# SCH_PCB_Dashboy_subboard_2023-03-20.net
KiCad netlist of a schematic drawn in EasyEDA
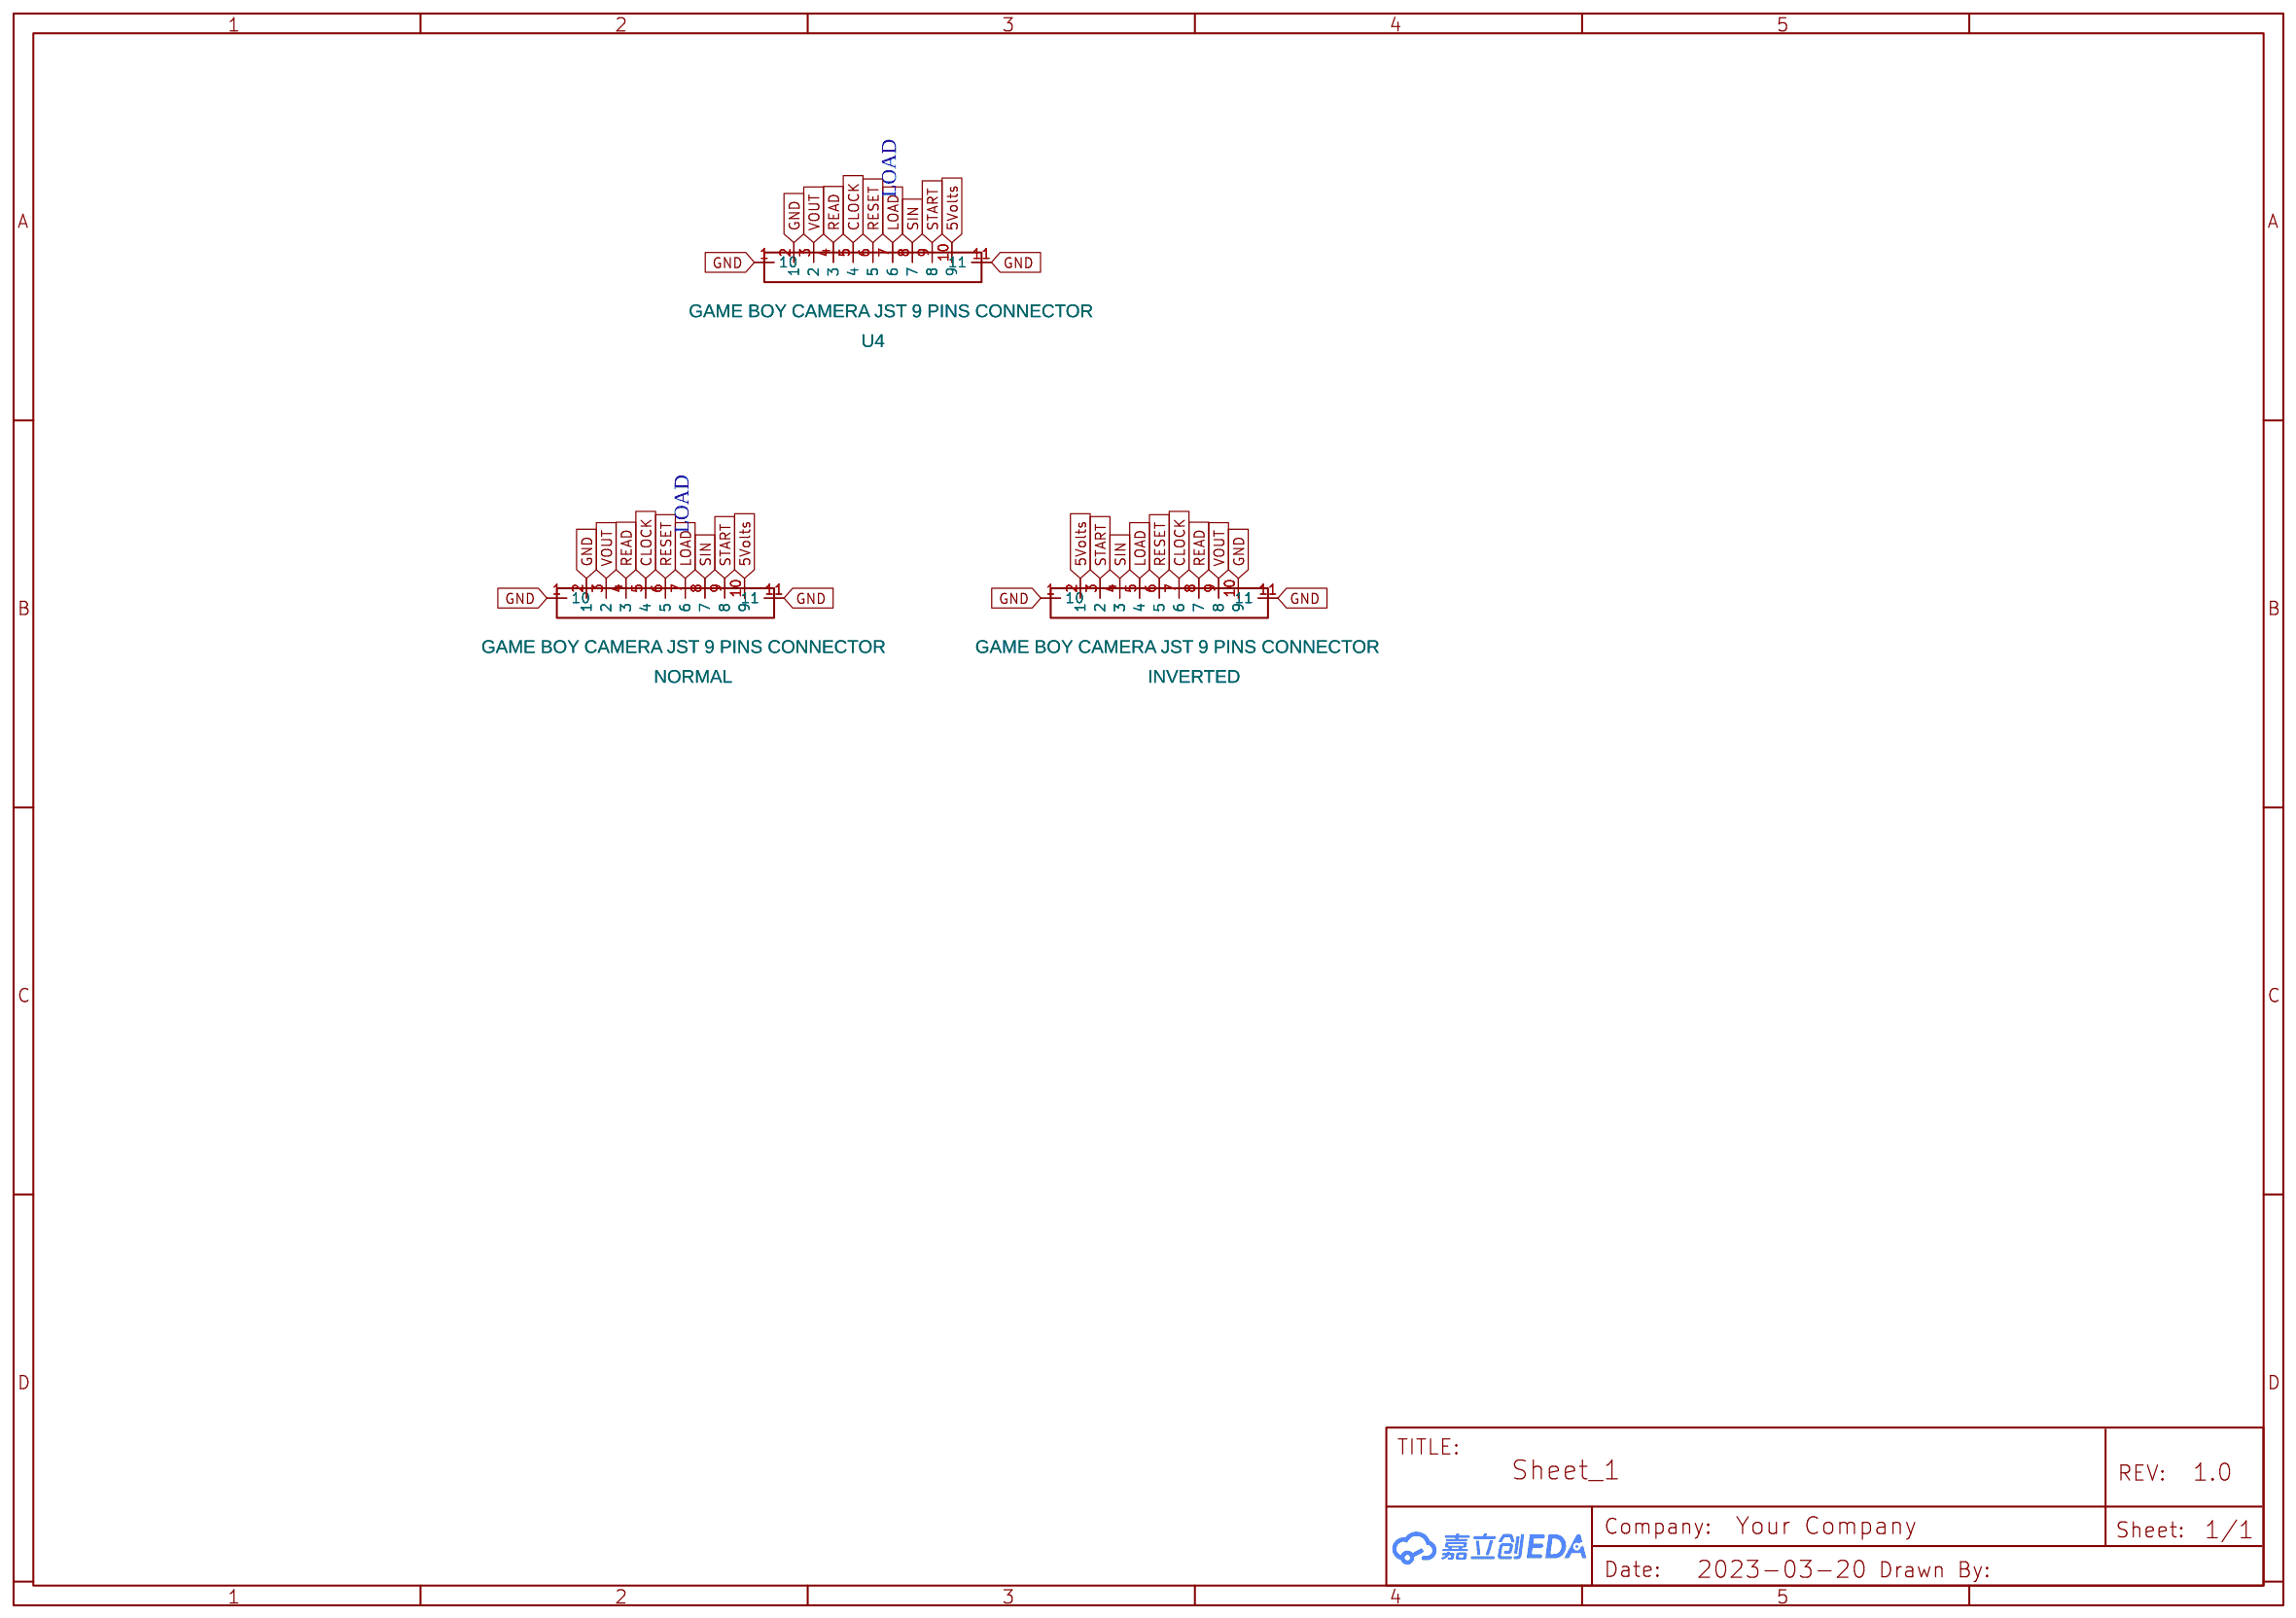
[diagram p0: schematic sheet]

(export (version "E")
  (design (tool "Eeschema 10.0.6"))
  (components
    (comp (ref "INVERTED")
      (value "GAME BOY CAMERA JST 9 PINS CONNECTOR")
      (libsource (lib "") (part "GAME BOY CAMERA JST 9 PINS CONNECTOR_1"))
    )
    (comp (ref "NORMAL")
      (value "GAME BOY CAMERA JST 9 PINS CONNECTOR")
      (libsource (lib "") (part "GAME BOY CAMERA JST 9 PINS CONNECTOR_2"))
    )
    (comp (ref "U4")
      (value "GAME BOY CAMERA JST 9 PINS CONNECTOR")
      (libsource (lib "") (part "GAME BOY CAMERA JST 9 PINS CONNECTOR"))
    )
  )
  (nets
    (net (code "1") (name "5Volts") (class "Default")
      (node (ref "INVERTED") (pin "2") (pinfunction "1_2") (pintype "unspecified"))
      (node (ref "NORMAL") (pin "10") (pinfunction "9_10") (pintype "unspecified"))
      (node (ref "U4") (pin "10") (pinfunction "9_10") (pintype "unspecified"))
    )
    (net (code "2") (name "CLOCK") (class "Default")
      (node (ref "INVERTED") (pin "7") (pinfunction "6_7") (pintype "unspecified"))
      (node (ref "NORMAL") (pin "5") (pinfunction "4_5") (pintype "unspecified"))
      (node (ref "U4") (pin "5") (pinfunction "4_5") (pintype "unspecified"))
    )
    (net (code "3") (name "GND") (class "Default")
      (node (ref "INVERTED") (pin "1") (pinfunction "10_1") (pintype "unspecified"))
      (node (ref "INVERTED") (pin "10") (pinfunction "9_10") (pintype "unspecified"))
      (node (ref "INVERTED") (pin "11") (pinfunction "11_11") (pintype "unspecified"))
      (node (ref "NORMAL") (pin "1") (pinfunction "10_1") (pintype "unspecified"))
      (node (ref "NORMAL") (pin "11") (pinfunction "11_11") (pintype "unspecified"))
      (node (ref "NORMAL") (pin "2") (pinfunction "1_2") (pintype "unspecified"))
      (node (ref "U4") (pin "1") (pinfunction "10_1") (pintype "unspecified"))
      (node (ref "U4") (pin "11") (pinfunction "11_11") (pintype "unspecified"))
      (node (ref "U4") (pin "2") (pinfunction "1_2") (pintype "unspecified"))
    )
    (net (code "4") (name "LOAD") (class "Default")
      (node (ref "INVERTED") (pin "5") (pinfunction "4_5") (pintype "unspecified"))
      (node (ref "NORMAL") (pin "7") (pinfunction "6_7") (pintype "unspecified"))
      (node (ref "U4") (pin "7") (pinfunction "6_7") (pintype "unspecified"))
    )
    (net (code "5") (name "READ") (class "Default")
      (node (ref "INVERTED") (pin "8") (pinfunction "7_8") (pintype "unspecified"))
      (node (ref "NORMAL") (pin "4") (pinfunction "3_4") (pintype "unspecified"))
      (node (ref "U4") (pin "4") (pinfunction "3_4") (pintype "unspecified"))
    )
    (net (code "6") (name "RESET") (class "Default")
      (node (ref "INVERTED") (pin "6") (pinfunction "5_6") (pintype "unspecified"))
      (node (ref "NORMAL") (pin "6") (pinfunction "5_6") (pintype "unspecified"))
      (node (ref "U4") (pin "6") (pinfunction "5_6") (pintype "unspecified"))
    )
    (net (code "7") (name "SIN") (class "Default")
      (node (ref "INVERTED") (pin "4") (pinfunction "3_4") (pintype "unspecified"))
      (node (ref "NORMAL") (pin "8") (pinfunction "7_8") (pintype "unspecified"))
      (node (ref "U4") (pin "8") (pinfunction "7_8") (pintype "unspecified"))
    )
    (net (code "8") (name "START") (class "Default")
      (node (ref "INVERTED") (pin "3") (pinfunction "2_3") (pintype "unspecified"))
      (node (ref "NORMAL") (pin "9") (pinfunction "8_9") (pintype "unspecified"))
      (node (ref "U4") (pin "9") (pinfunction "8_9") (pintype "unspecified"))
    )
    (net (code "9") (name "VOUT") (class "Default")
      (node (ref "INVERTED") (pin "9") (pinfunction "8_9") (pintype "unspecified"))
      (node (ref "NORMAL") (pin "3") (pinfunction "2_3") (pintype "unspecified"))
      (node (ref "U4") (pin "3") (pinfunction "2_3") (pintype "unspecified"))
    )
  )
)
